# avoccado-avr-pcb-micro-a1.net
KiCad netlist of a schematic drawn in EAGLE
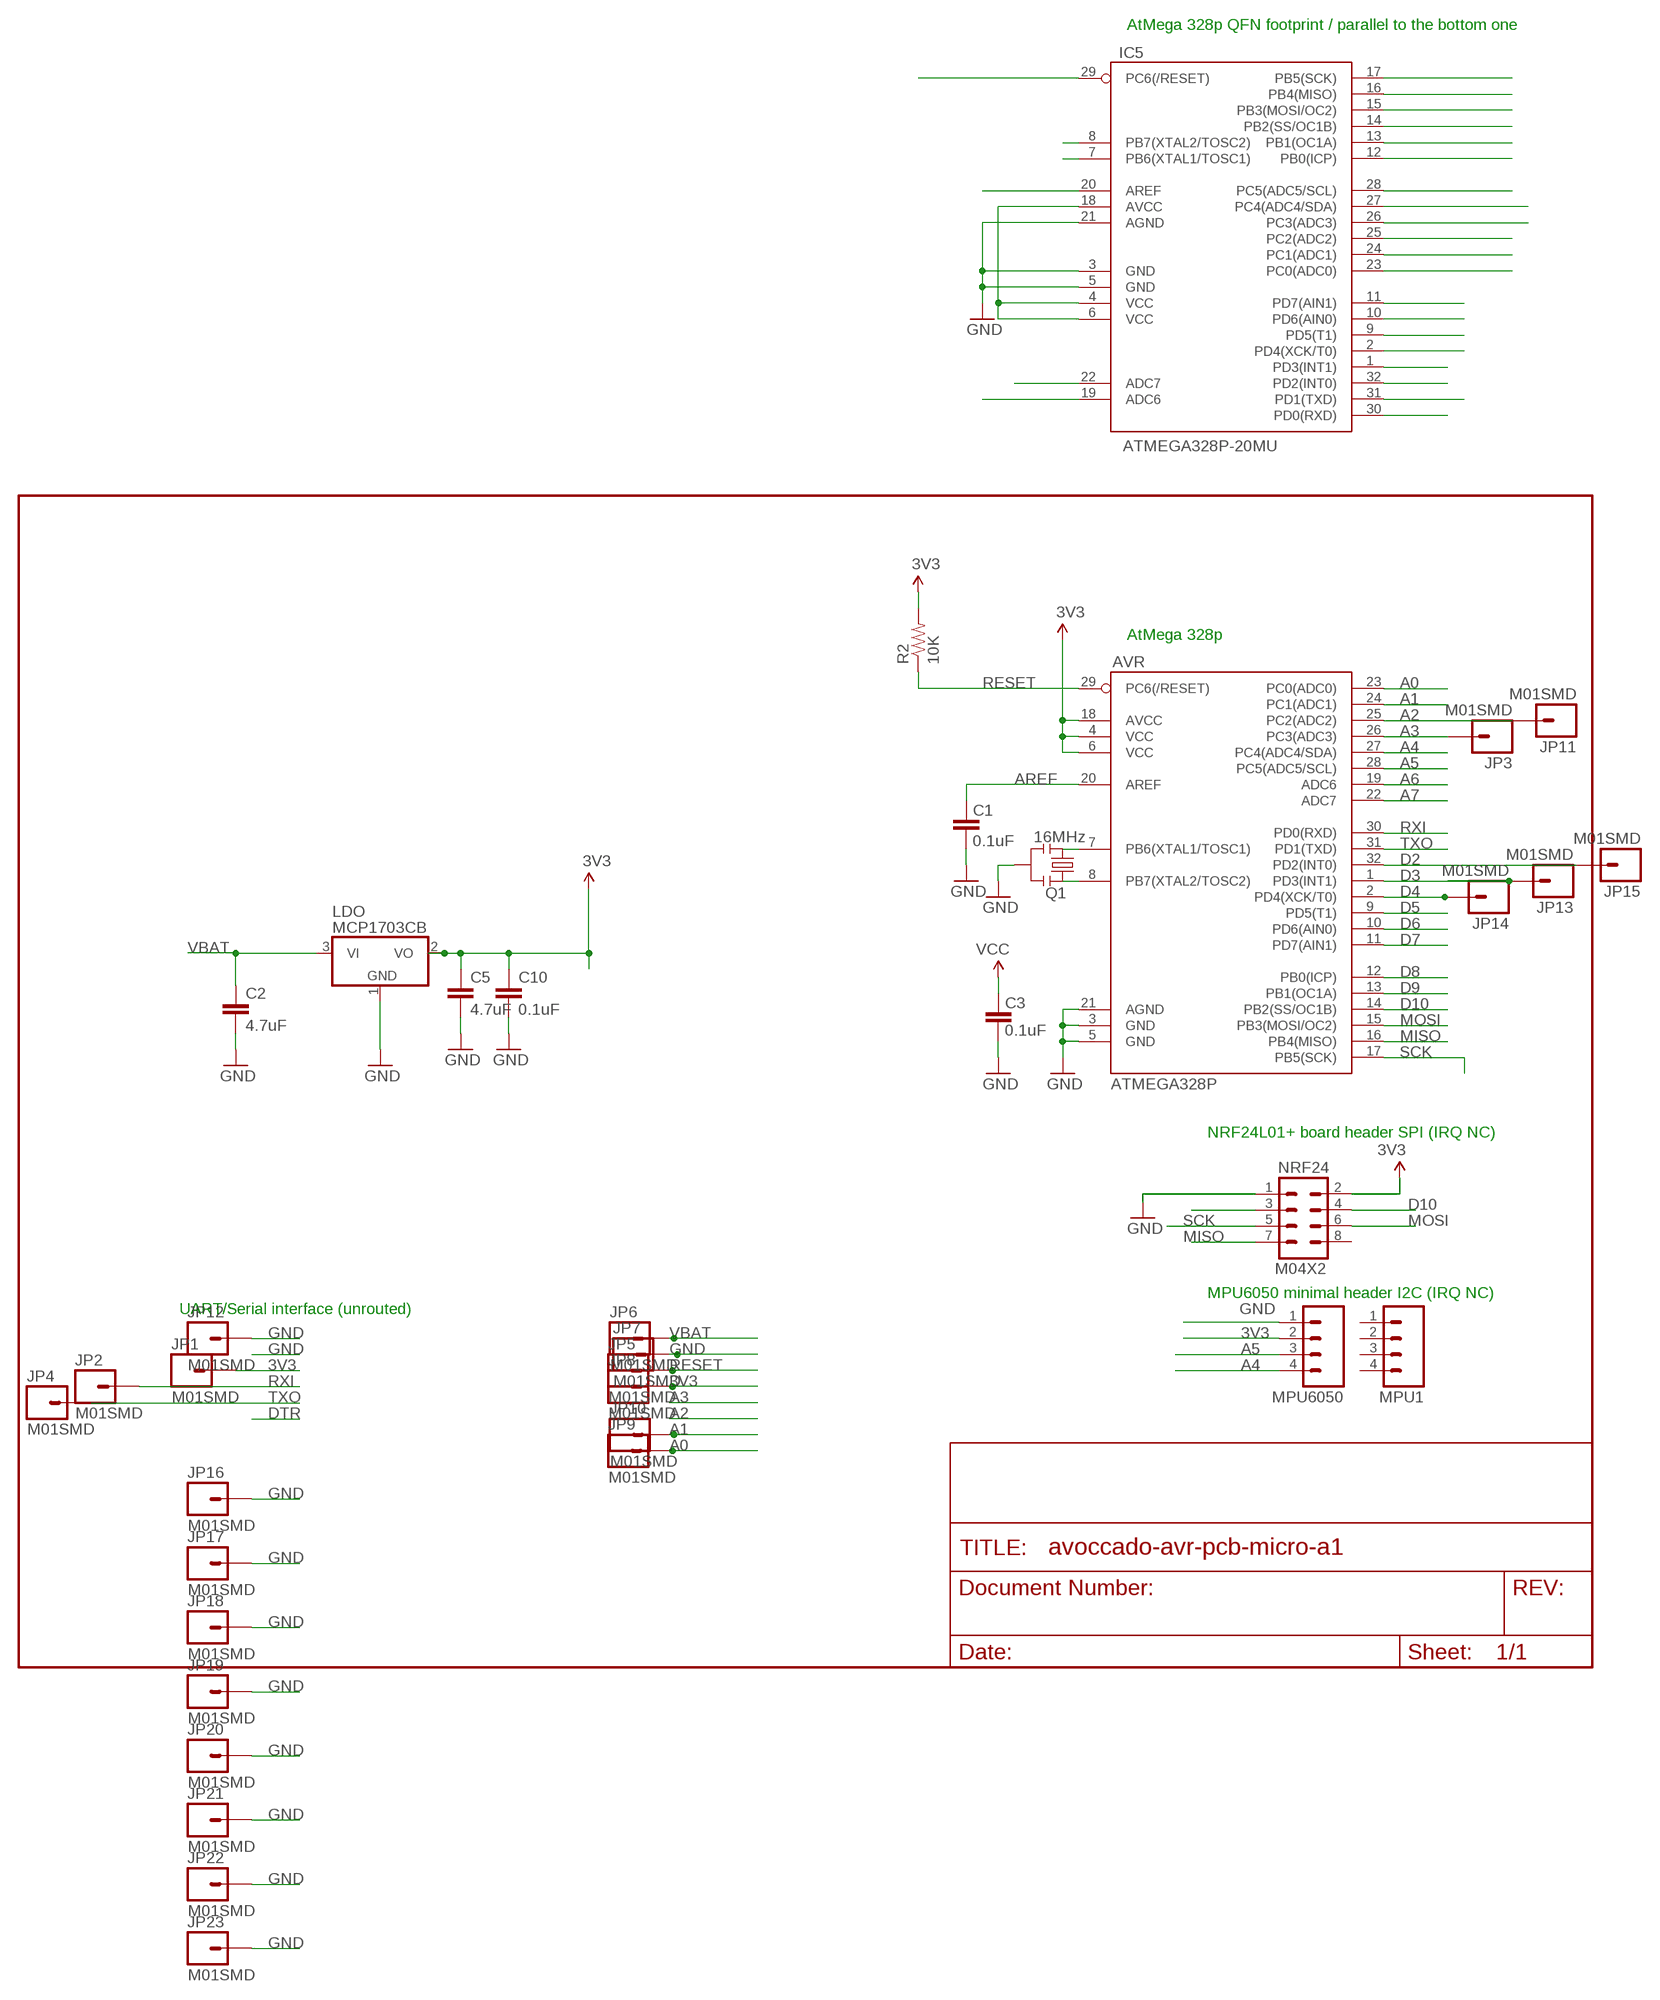
[diagram p0: schematic, sheet 1]

(export (version "E")
  (design (tool "Eeschema 10.0.6"))
  (components
    (comp (ref "AVR")
      (value "ATMEGA328P")
      (footprint "eagle-import:TQFP32-08")
      (libsource (lib "eagle-import") (part "ATMEGA328_SMT"))
    )
    (comp (ref "C1")
      (value "0.1uF")
      (footprint "eagle-import:C0402")
      (libsource (lib "eagle-import") (part "CAP0402"))
    )
    (comp (ref "C2")
      (value "4.7uF")
      (footprint "eagle-import:0603-CAP")
      (libsource (lib "eagle-import") (part "4.7UF-6.3V-10%(0603)0603"))
    )
    (comp (ref "C3")
      (value "0.1uF")
      (footprint "eagle-import:C0402")
      (libsource (lib "eagle-import") (part "CAP0402"))
    )
    (comp (ref "C5")
      (value "4.7uF")
      (footprint "eagle-import:0603-CAP")
      (libsource (lib "eagle-import") (part "4.7UF-6.3V-10%(0603)0603"))
    )
    (comp (ref "C10")
      (value "0.1uF")
      (footprint "eagle-import:C0402")
      (libsource (lib "eagle-import") (part "CAP0402"))
    )
    (comp (ref "IC5")
      (value "ATMEGA328P-20MU")
      (footprint "eagle-import:MLF32")
      (libsource (lib "eagle-import") (part "MEGA8-MI"))
    )
    (comp (ref "JP1")
      (value "M01SMD")
      (footprint "eagle-import:LUXEON-PAD")
      (libsource (lib "eagle-import") (part "M01SMD"))
    )
    (comp (ref "JP2")
      (value "M01SMD")
      (footprint "eagle-import:LUXEON-PAD")
      (libsource (lib "eagle-import") (part "M01SMD"))
    )
    (comp (ref "JP3")
      (value "M01SMD")
      (footprint "eagle-import:LUXEON-PAD")
      (libsource (lib "eagle-import") (part "M01SMD"))
    )
    (comp (ref "JP4")
      (value "M01SMD")
      (footprint "eagle-import:LUXEON-PAD")
      (libsource (lib "eagle-import") (part "M01SMD"))
    )
    (comp (ref "JP5")
      (value "M01SMD")
      (footprint "eagle-import:LUXEON-PAD")
      (libsource (lib "eagle-import") (part "M01SMD"))
    )
    (comp (ref "JP6")
      (value "M01SMD")
      (footprint "eagle-import:LUXEON-PAD")
      (libsource (lib "eagle-import") (part "M01SMD"))
    )
    (comp (ref "JP7")
      (value "M01SMD")
      (footprint "eagle-import:LUXEON-PAD")
      (libsource (lib "eagle-import") (part "M01SMD"))
    )
    (comp (ref "JP8")
      (value "M01SMD")
      (footprint "eagle-import:LUXEON-PAD")
      (libsource (lib "eagle-import") (part "M01SMD"))
    )
    (comp (ref "JP9")
      (value "M01SMD")
      (footprint "eagle-import:LUXEON-PAD")
      (libsource (lib "eagle-import") (part "M01SMD"))
    )
    (comp (ref "JP10")
      (value "M01SMD")
      (footprint "eagle-import:LUXEON-PAD")
      (libsource (lib "eagle-import") (part "M01SMD"))
    )
    (comp (ref "JP11")
      (value "M01SMD")
      (footprint "eagle-import:LUXEON-PAD")
      (libsource (lib "eagle-import") (part "M01SMD"))
    )
    (comp (ref "JP12")
      (value "M01SMD")
      (footprint "eagle-import:LUXEON-PAD")
      (libsource (lib "eagle-import") (part "M01SMD"))
    )
    (comp (ref "JP13")
      (value "M01SMD")
      (footprint "eagle-import:LUXEON-PAD")
      (libsource (lib "eagle-import") (part "M01SMD"))
    )
    (comp (ref "JP14")
      (value "M01SMD")
      (footprint "eagle-import:LUXEON-PAD")
      (libsource (lib "eagle-import") (part "M01SMD"))
    )
    (comp (ref "JP15")
      (value "M01SMD")
      (footprint "eagle-import:LUXEON-PAD")
      (libsource (lib "eagle-import") (part "M01SMD"))
    )
    (comp (ref "JP16")
      (value "M01SMD")
      (footprint "eagle-import:LUXEON-PAD")
      (libsource (lib "eagle-import") (part "M01SMD"))
    )
    (comp (ref "JP17")
      (value "M01SMD")
      (footprint "eagle-import:LUXEON-PAD")
      (libsource (lib "eagle-import") (part "M01SMD"))
    )
    (comp (ref "JP18")
      (value "M01SMD")
      (footprint "eagle-import:LUXEON-PAD")
      (libsource (lib "eagle-import") (part "M01SMD"))
    )
    (comp (ref "JP19")
      (value "M01SMD")
      (footprint "eagle-import:LUXEON-PAD")
      (libsource (lib "eagle-import") (part "M01SMD"))
    )
    (comp (ref "JP20")
      (value "M01SMD")
      (footprint "eagle-import:LUXEON-PAD")
      (libsource (lib "eagle-import") (part "M01SMD"))
    )
    (comp (ref "JP21")
      (value "M01SMD")
      (footprint "eagle-import:LUXEON-PAD")
      (libsource (lib "eagle-import") (part "M01SMD"))
    )
    (comp (ref "JP22")
      (value "M01SMD")
      (footprint "eagle-import:LUXEON-PAD")
      (libsource (lib "eagle-import") (part "M01SMD"))
    )
    (comp (ref "JP23")
      (value "M01SMD")
      (footprint "eagle-import:LUXEON-PAD")
      (libsource (lib "eagle-import") (part "M01SMD"))
    )
    (comp (ref "LDO")
      (value "MCP1703CB")
      (footprint "eagle-import:SOT23")
      (libsource (lib "eagle-import") (part "MCP1703CB"))
    )
    (comp (ref "MPU1")
      (value "M041X04_NO_SILK")
      (footprint "eagle-import:1X04_NO_SILK")
      (libsource (lib "eagle-import") (part "M041X04_NO_SILK"))
    )
    (comp (ref "MPU6050")
      (value "M041X04_NO_SILK")
      (footprint "eagle-import:1X04_NO_SILK")
      (libsource (lib "eagle-import") (part "M041X04_NO_SILK"))
    )
    (comp (ref "NRF24")
      (value "M04X2")
      (footprint "eagle-import:2X4")
      (libsource (lib "eagle-import") (part "M04X2"))
    )
    (comp (ref "Q1")
      (value "16MHz")
      (footprint "eagle-import:RESONATOR-SMD")
      (libsource (lib "eagle-import") (part "RESONATORSMD"))
    )
    (comp (ref "R2")
      (value "10K")
      (footprint "eagle-import:0603-RES")
      (libsource (lib "eagle-import") (part "RESISTOR0603"))
    )
  )
  (nets
    (net (code "1") (name "/A0") (class "Default")
      (node (ref "AVR") (pin "23") (pinfunction "PC0(ADC0)_23") (pintype "bidirectional"))
      (node (ref "IC5") (pin "23") (pinfunction "PC0(ADC0)_23") (pintype "bidirectional"))
      (node (ref "JP9") (pin "P$1") (pinfunction "1_P$1") (pintype "passive"))
    )
    (net (code "2") (name "/A1") (class "Default")
      (node (ref "AVR") (pin "24") (pinfunction "PC1(ADC1)_24") (pintype "bidirectional"))
      (node (ref "IC5") (pin "24") (pinfunction "PC1(ADC1)_24") (pintype "bidirectional"))
      (node (ref "JP10") (pin "P$1") (pinfunction "1_P$1") (pintype "passive"))
    )
    (net (code "3") (name "/A2") (class "Default")
      (node (ref "AVR") (pin "25") (pinfunction "PC2(ADC2)_25") (pintype "bidirectional"))
      (node (ref "IC5") (pin "25") (pinfunction "PC2(ADC2)_25") (pintype "bidirectional"))
      (node (ref "JP11") (pin "P$1") (pinfunction "1_P$1") (pintype "passive"))
    )
    (net (code "4") (name "/A3") (class "Default")
      (node (ref "AVR") (pin "26") (pinfunction "PC3(ADC3)_26") (pintype "bidirectional"))
      (node (ref "IC5") (pin "26") (pinfunction "PC3(ADC3)_26") (pintype "bidirectional"))
      (node (ref "JP3") (pin "P$1") (pinfunction "1_P$1") (pintype "passive"))
    )
    (net (code "5") (name "/A4") (class "Default")
      (node (ref "AVR") (pin "27") (pinfunction "PC4(ADC4/SDA)_27") (pintype "bidirectional"))
      (node (ref "IC5") (pin "27") (pinfunction "PC4(ADC4/SDA)_27") (pintype "bidirectional"))
      (node (ref "MPU6050") (pin "4") (pinfunction "4_4") (pintype "passive"))
    )
    (net (code "6") (name "/A5") (class "Default")
      (node (ref "AVR") (pin "28") (pinfunction "PC5(ADC5/SCL)_28") (pintype "bidirectional"))
      (node (ref "IC5") (pin "28") (pinfunction "PC5(ADC5/SCL)_28") (pintype "bidirectional"))
      (node (ref "MPU6050") (pin "3") (pinfunction "3_3") (pintype "passive"))
    )
    (net (code "7") (name "/A6") (class "Default")
      (node (ref "AVR") (pin "19") (pinfunction "ADC6_19") (pintype "bidirectional"))
      (node (ref "IC5") (pin "19") (pinfunction "ADC6_19") (pintype "bidirectional"))
    )
    (net (code "8") (name "/A7") (class "Default")
      (node (ref "AVR") (pin "22") (pinfunction "ADC7_22") (pintype "bidirectional"))
      (node (ref "IC5") (pin "22") (pinfunction "ADC7_22") (pintype "bidirectional"))
    )
    (net (code "9") (name "/AREF") (class "Default")
      (node (ref "AVR") (pin "20") (pinfunction "AREF_20") (pintype "bidirectional"))
      (node (ref "C1") (pin "2") (pinfunction "2_2") (pintype "passive"))
      (node (ref "IC5") (pin "20") (pinfunction "AREF_20") (pintype "bidirectional"))
    )
    (net (code "10") (name "/D2") (class "Default")
      (node (ref "AVR") (pin "32") (pinfunction "PD2(INT0)_32") (pintype "bidirectional"))
      (node (ref "IC5") (pin "32") (pinfunction "PD2(INT0)_32") (pintype "bidirectional"))
      (node (ref "JP15") (pin "P$1") (pinfunction "1_P$1") (pintype "passive"))
    )
    (net (code "11") (name "/D3") (class "Default")
      (node (ref "AVR") (pin "1") (pinfunction "PD3(INT1)_1") (pintype "bidirectional"))
      (node (ref "IC5") (pin "1") (pinfunction "PD3(INT1)_1") (pintype "bidirectional"))
      (node (ref "JP13") (pin "P$1") (pinfunction "1_P$1") (pintype "passive"))
    )
    (net (code "12") (name "/D4") (class "Default")
      (node (ref "AVR") (pin "2") (pinfunction "PD4(XCK/T0)_2") (pintype "bidirectional"))
      (node (ref "IC5") (pin "2") (pinfunction "PD4(XCK/T0)_2") (pintype "bidirectional"))
      (node (ref "JP14") (pin "P$1") (pinfunction "1_P$1") (pintype "passive"))
    )
    (net (code "13") (name "/D5") (class "Default")
      (node (ref "AVR") (pin "9") (pinfunction "PD5(T1)_9") (pintype "bidirectional"))
      (node (ref "IC5") (pin "9") (pinfunction "PD5(T1)_9") (pintype "bidirectional"))
    )
    (net (code "14") (name "/D6") (class "Default")
      (node (ref "AVR") (pin "10") (pinfunction "PD6(AIN0)_10") (pintype "bidirectional"))
      (node (ref "IC5") (pin "10") (pinfunction "PD6(AIN0)_10") (pintype "bidirectional"))
    )
    (net (code "15") (name "/D7") (class "Default")
      (node (ref "AVR") (pin "11") (pinfunction "PD7(AIN1)_11") (pintype "bidirectional"))
      (node (ref "IC5") (pin "11") (pinfunction "PD7(AIN1)_11") (pintype "bidirectional"))
    )
    (net (code "16") (name "/D8") (class "Default")
      (node (ref "AVR") (pin "12") (pinfunction "PB0(ICP)_12") (pintype "bidirectional"))
      (node (ref "IC5") (pin "12") (pinfunction "PB0(ICP)_12") (pintype "bidirectional"))
    )
    (net (code "17") (name "/D9") (class "Default")
      (node (ref "AVR") (pin "13") (pinfunction "PB1(OC1A)_13") (pintype "bidirectional"))
      (node (ref "IC5") (pin "13") (pinfunction "PB1(OC1A)_13") (pintype "bidirectional"))
      (node (ref "NRF24") (pin "3") (pinfunction "3_3") (pintype "passive"))
    )
    (net (code "18") (name "/D10") (class "Default")
      (node (ref "AVR") (pin "14") (pinfunction "PB2(SS/OC1B)_14") (pintype "bidirectional"))
      (node (ref "IC5") (pin "14") (pinfunction "PB2(SS/OC1B)_14") (pintype "bidirectional"))
      (node (ref "NRF24") (pin "4") (pinfunction "4_4") (pintype "passive"))
    )
    (net (code "20") (name "/MISO") (class "Default")
      (node (ref "AVR") (pin "16") (pinfunction "PB4(MISO)_16") (pintype "bidirectional"))
      (node (ref "IC5") (pin "16") (pinfunction "PB4(MISO)_16") (pintype "bidirectional"))
      (node (ref "NRF24") (pin "7") (pinfunction "7_7") (pintype "passive"))
    )
    (net (code "21") (name "/MOSI") (class "Default")
      (node (ref "AVR") (pin "15") (pinfunction "PB3(MOSI/OC2)_15") (pintype "bidirectional"))
      (node (ref "IC5") (pin "15") (pinfunction "PB3(MOSI/OC2)_15") (pintype "bidirectional"))
      (node (ref "NRF24") (pin "6") (pinfunction "6_6") (pintype "passive"))
    )
    (net (code "22") (name "/N$1") (class "Default")
      (node (ref "AVR") (pin "8") (pinfunction "PB7(XTAL2/TOSC2)_8") (pintype "bidirectional"))
      (node (ref "IC5") (pin "8") (pinfunction "PB7(XTAL2/TOSC2)_8") (pintype "bidirectional"))
      (node (ref "Q1") (pin "1") (pinfunction "1_1") (pintype "passive"))
    )
    (net (code "23") (name "/N$2") (class "Default")
      (node (ref "AVR") (pin "7") (pinfunction "PB6(XTAL1/TOSC1)_7") (pintype "bidirectional"))
      (node (ref "IC5") (pin "7") (pinfunction "PB6(XTAL1/TOSC1)_7") (pintype "bidirectional"))
      (node (ref "Q1") (pin "3") (pinfunction "3_3") (pintype "passive"))
    )
    (net (code "24") (name "/RESET") (class "Default")
      (node (ref "AVR") (pin "29") (pinfunction "PC6(/RESET)_29") (pintype "bidirectional"))
      (node (ref "IC5") (pin "29") (pinfunction "PC6(/RESET)_29") (pintype "bidirectional"))
      (node (ref "JP5") (pin "P$1") (pinfunction "1_P$1") (pintype "passive"))
      (node (ref "R2") (pin "1") (pinfunction "1_1") (pintype "passive"))
    )
    (net (code "25") (name "/RXI") (class "Default")
      (node (ref "AVR") (pin "30") (pinfunction "PD0(RXD)_30") (pintype "bidirectional"))
      (node (ref "IC5") (pin "30") (pinfunction "PD0(RXD)_30") (pintype "bidirectional"))
      (node (ref "JP2") (pin "P$1") (pinfunction "1_P$1") (pintype "passive"))
    )
    (net (code "26") (name "/SCK") (class "Default")
      (node (ref "AVR") (pin "17") (pinfunction "PB5(SCK)_17") (pintype "bidirectional"))
      (node (ref "IC5") (pin "17") (pinfunction "PB5(SCK)_17") (pintype "bidirectional"))
      (node (ref "NRF24") (pin "5") (pinfunction "5_5") (pintype "passive"))
    )
    (net (code "27") (name "/TXO") (class "Default")
      (node (ref "AVR") (pin "31") (pinfunction "PD1(TXD)_31") (pintype "bidirectional"))
      (node (ref "IC5") (pin "31") (pinfunction "PD1(TXD)_31") (pintype "bidirectional"))
      (node (ref "JP4") (pin "P$1") (pinfunction "1_P$1") (pintype "passive"))
    )
    (net (code "28") (name "/VBAT") (class "Default")
      (node (ref "C2") (pin "1") (pinfunction "1_1") (pintype "passive"))
      (node (ref "JP6") (pin "P$1") (pinfunction "1_P$1") (pintype "passive"))
      (node (ref "LDO") (pin "3") (pinfunction "VI_3") (pintype "input"))
    )
    (net (code "29") (name "3V3") (class "Default")
      (node (ref "AVR") (pin "18") (pinfunction "AVCC_18") (pintype "bidirectional"))
      (node (ref "AVR") (pin "4") (pinfunction "VCC_4") (pintype "bidirectional"))
      (node (ref "AVR") (pin "6") (pinfunction "VCC_6") (pintype "bidirectional"))
      (node (ref "C10") (pin "1") (pinfunction "1_1") (pintype "passive"))
      (node (ref "C3") (pin "2") (pinfunction "2_2") (pintype "passive"))
      (node (ref "C5") (pin "1") (pinfunction "1_1") (pintype "passive"))
      (node (ref "IC5") (pin "18") (pinfunction "AVCC_18") (pintype "bidirectional"))
      (node (ref "IC5") (pin "4") (pinfunction "VCC_4") (pintype "bidirectional"))
      (node (ref "IC5") (pin "6") (pinfunction "VCC_6") (pintype "bidirectional"))
      (node (ref "JP1") (pin "P$1") (pinfunction "1_P$1") (pintype "passive"))
      (node (ref "JP8") (pin "P$1") (pinfunction "1_P$1") (pintype "passive"))
      (node (ref "LDO") (pin "2") (pinfunction "VO_2") (pintype "passive"))
      (node (ref "MPU6050") (pin "2") (pinfunction "2_2") (pintype "passive"))
      (node (ref "NRF24") (pin "2") (pinfunction "2_2") (pintype "passive"))
      (node (ref "R2") (pin "2") (pinfunction "2_2") (pintype "passive"))
    )
    (net (code "30") (name "GND") (class "Default")
      (node (ref "AVR") (pin "21") (pinfunction "AGND_21") (pintype "bidirectional"))
      (node (ref "AVR") (pin "3") (pinfunction "GND_3") (pintype "bidirectional"))
      (node (ref "AVR") (pin "5") (pinfunction "GND_5") (pintype "bidirectional"))
      (node (ref "C1") (pin "1") (pinfunction "1_1") (pintype "passive"))
      (node (ref "C10") (pin "2") (pinfunction "2_2") (pintype "passive"))
      (node (ref "C2") (pin "2") (pinfunction "2_2") (pintype "passive"))
      (node (ref "C3") (pin "1") (pinfunction "1_1") (pintype "passive"))
      (node (ref "C5") (pin "2") (pinfunction "2_2") (pintype "passive"))
      (node (ref "IC5") (pin "21") (pinfunction "AGND_21") (pintype "bidirectional"))
      (node (ref "IC5") (pin "3") (pinfunction "GND_3") (pintype "bidirectional"))
      (node (ref "IC5") (pin "5") (pinfunction "GND_5") (pintype "bidirectional"))
      (node (ref "JP12") (pin "P$1") (pinfunction "1_P$1") (pintype "passive"))
      (node (ref "JP16") (pin "P$1") (pinfunction "1_P$1") (pintype "passive"))
      (node (ref "JP17") (pin "P$1") (pinfunction "1_P$1") (pintype "passive"))
      (node (ref "JP18") (pin "P$1") (pinfunction "1_P$1") (pintype "passive"))
      (node (ref "JP19") (pin "P$1") (pinfunction "1_P$1") (pintype "passive"))
      (node (ref "JP20") (pin "P$1") (pinfunction "1_P$1") (pintype "passive"))
      (node (ref "JP21") (pin "P$1") (pinfunction "1_P$1") (pintype "passive"))
      (node (ref "JP22") (pin "P$1") (pinfunction "1_P$1") (pintype "passive"))
      (node (ref "JP23") (pin "P$1") (pinfunction "1_P$1") (pintype "passive"))
      (node (ref "JP7") (pin "P$1") (pinfunction "1_P$1") (pintype "passive"))
      (node (ref "LDO") (pin "1") (pinfunction "GND_1") (pintype "passive"))
      (node (ref "MPU6050") (pin "1") (pinfunction "1_1") (pintype "passive"))
      (node (ref "NRF24") (pin "1") (pinfunction "1_1") (pintype "passive"))
      (node (ref "Q1") (pin "2") (pinfunction "2_2") (pintype "passive"))
    )
    (net (code "31") (name "unconnected-(MPU1-Pad1)") (class "Default")
      (node (ref "MPU1") (pin "1") (pinfunction "1_1") (pintype "passive"))
    )
    (net (code "32") (name "unconnected-(MPU1-Pad2)") (class "Default")
      (node (ref "MPU1") (pin "2") (pinfunction "2_2") (pintype "passive"))
    )
    (net (code "33") (name "unconnected-(MPU1-Pad3)") (class "Default")
      (node (ref "MPU1") (pin "3") (pinfunction "3_3") (pintype "passive"))
    )
    (net (code "34") (name "unconnected-(MPU1-Pad4)") (class "Default")
      (node (ref "MPU1") (pin "4") (pinfunction "4_4") (pintype "passive"))
    )
    (net (code "35") (name "unconnected-(NRF24-Pad8)") (class "Default")
      (node (ref "NRF24") (pin "8") (pinfunction "8_8") (pintype "passive"))
    )
  )
)
